# Board-Back.net
KiCad netlist of a schematic drawn in EAGLE
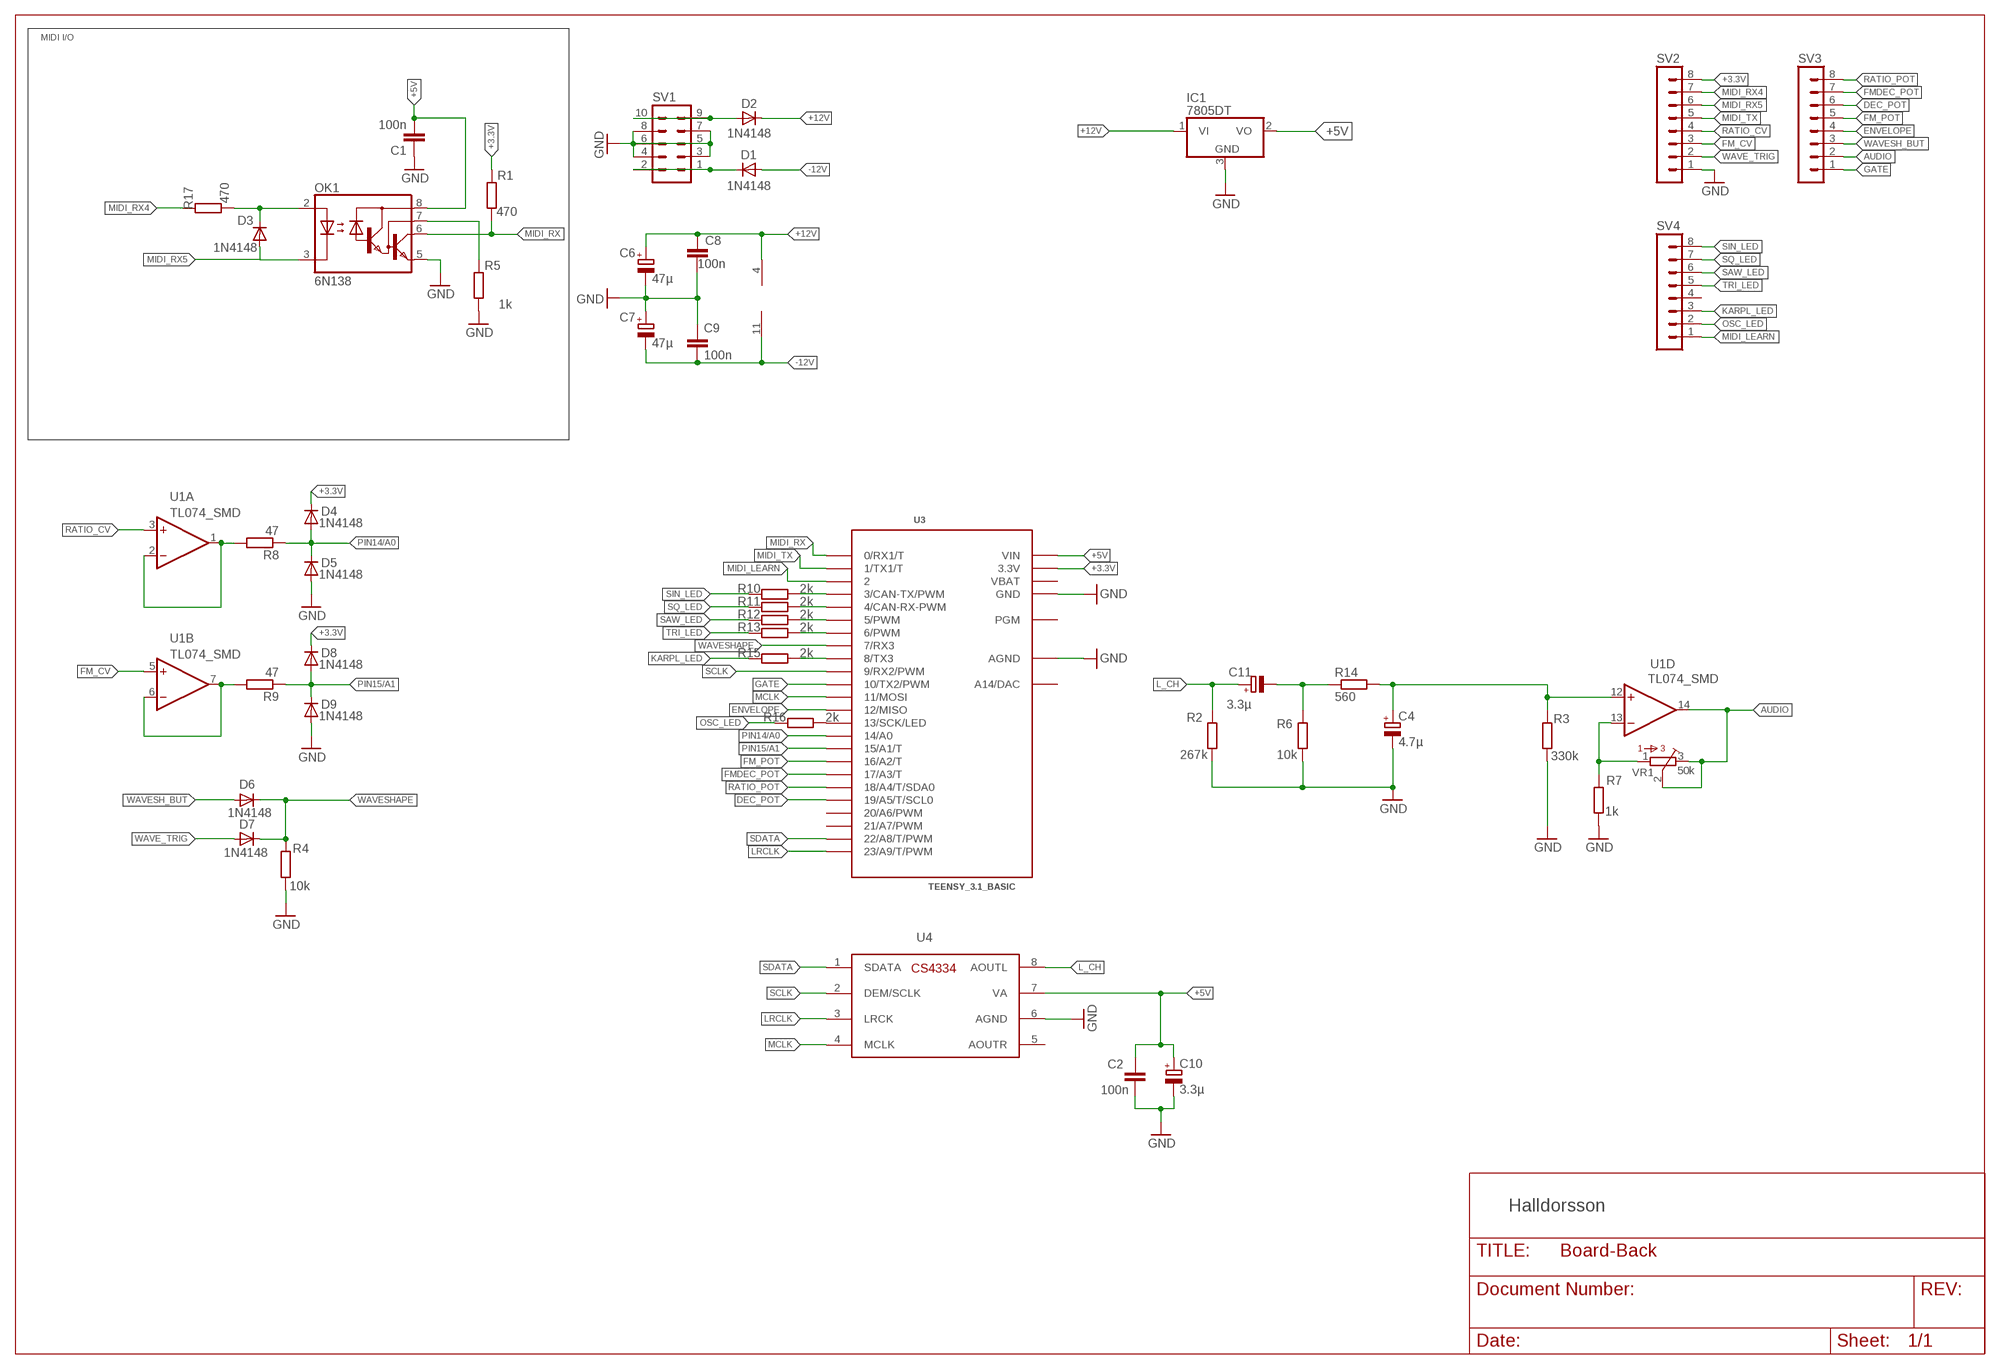
[diagram p0: schematic, sheet 1]

(export (version "E")
  (design (tool "Eeschema 10.0.6"))
  (components
    (comp (ref "C1")
      (value "100n")
      (footprint "eagle-import:C1206")
      (libsource (lib "eagle-import") (part "C-EUC1206"))
    )
    (comp (ref "C2")
      (value "100n")
      (footprint "eagle-import:C1206")
      (libsource (lib "eagle-import") (part "C-EUC1206"))
    )
    (comp (ref "C4")
      (value "4.7µ♦")
      (footprint "eagle-import:153CLV-0405")
      (libsource (lib "eagle-import") (part "CPOL-EU153CLV-0405"))
    )
    (comp (ref "C6")
      (value "47µ")
      (footprint "eagle-import:E5-6")
      (libsource (lib "eagle-import") (part "CPOL-EUE5-6"))
    )
    (comp (ref "C7")
      (value "47µ")
      (footprint "eagle-import:E5-6")
      (libsource (lib "eagle-import") (part "CPOL-EUE5-6"))
    )
    (comp (ref "C8")
      (value "100n")
      (footprint "eagle-import:C1206")
      (libsource (lib "eagle-import") (part "C-EUC1206"))
    )
    (comp (ref "C9")
      (value "100n")
      (footprint "eagle-import:C1206")
      (libsource (lib "eagle-import") (part "C-EUC1206"))
    )
    (comp (ref "C10")
      (value "3.3µ")
      (footprint "eagle-import:153CLV-0505")
      (libsource (lib "eagle-import") (part "CPOL-EU153CLV-0505"))
    )
    (comp (ref "C11")
      (value "3.3µ")
      (footprint "eagle-import:153CLV-0405")
      (libsource (lib "eagle-import") (part "CPOL-EU153CLV-0405"))
    )
    (comp (ref "D1")
      (value "1N4148")
      (footprint "eagle-import:DO35-7")
      (libsource (lib "eagle-import") (part "1N4148DO35-7"))
    )
    (comp (ref "D2")
      (value "1N4148")
      (footprint "eagle-import:DO35-7")
      (libsource (lib "eagle-import") (part "1N4148DO35-7"))
    )
    (comp (ref "D3")
      (value "1N4148")
      (footprint "eagle-import:DO35-7")
      (libsource (lib "eagle-import") (part "1N4148DO35-7"))
    )
    (comp (ref "D4")
      (value "1N4148")
      (footprint "eagle-import:DO35-7")
      (libsource (lib "eagle-import") (part "1N4148DO35-7"))
    )
    (comp (ref "D5")
      (value "1N4148")
      (footprint "eagle-import:DO35-7")
      (libsource (lib "eagle-import") (part "1N4148DO35-7"))
    )
    (comp (ref "D6")
      (value "1N4148")
      (footprint "eagle-import:DO35-7")
      (libsource (lib "eagle-import") (part "1N4148DO35-7"))
    )
    (comp (ref "D7")
      (value "1N4148")
      (footprint "eagle-import:DO35-7")
      (libsource (lib "eagle-import") (part "1N4148DO35-7"))
    )
    (comp (ref "D8")
      (value "1N4148")
      (footprint "eagle-import:DO35-7")
      (libsource (lib "eagle-import") (part "1N4148DO35-7"))
    )
    (comp (ref "D9")
      (value "1N4148")
      (footprint "eagle-import:DO35-7")
      (libsource (lib "eagle-import") (part "1N4148DO35-7"))
    )
    (comp (ref "IC1")
      (value "7805DT")
      (footprint "eagle-import:TO252")
      (libsource (lib "eagle-import") (part "78DT05"))
    )
    (comp (ref "OK1")
      (value "6N138")
      (footprint "eagle-import:DIL08")
      (fields (field (name "MF") "VISHAY/TELEFUNKEN"))
      (libsource (lib "eagle-import") (part "6N138"))
    )
    (comp (ref "R1")
      (value "470")
      (footprint "eagle-import:M1206")
      (libsource (lib "eagle-import") (part "R-EU_M1206"))
    )
    (comp (ref "R2")
      (value "267k")
      (footprint "eagle-import:M1206")
      (libsource (lib "eagle-import") (part "R-EU_M1206"))
    )
    (comp (ref "R3")
      (value "330k")
      (footprint "eagle-import:M1206")
      (libsource (lib "eagle-import") (part "R-EU_M1206"))
    )
    (comp (ref "R4")
      (value "10k")
      (footprint "eagle-import:M1206")
      (libsource (lib "eagle-import") (part "R-EU_M1206"))
    )
    (comp (ref "R5")
      (value "1k")
      (footprint "eagle-import:M1206")
      (libsource (lib "eagle-import") (part "R-EU_M1206"))
    )
    (comp (ref "R6")
      (value "10k")
      (footprint "eagle-import:M1206")
      (libsource (lib "eagle-import") (part "R-EU_M1206"))
    )
    (comp (ref "R7")
      (value "1k")
      (footprint "eagle-import:M1206")
      (libsource (lib "eagle-import") (part "R-EU_M1206"))
    )
    (comp (ref "R8")
      (value "47")
      (footprint "eagle-import:M1206")
      (libsource (lib "eagle-import") (part "R-EU_M1206"))
    )
    (comp (ref "R9")
      (value "47")
      (footprint "eagle-import:M1206")
      (libsource (lib "eagle-import") (part "R-EU_M1206"))
    )
    (comp (ref "R10")
      (value "2k")
      (footprint "eagle-import:M1206")
      (libsource (lib "eagle-import") (part "R-EU_M1206"))
    )
    (comp (ref "R11")
      (value "2k")
      (footprint "eagle-import:M1206")
      (libsource (lib "eagle-import") (part "R-EU_M1206"))
    )
    (comp (ref "R12")
      (value "2k")
      (footprint "eagle-import:M1206")
      (libsource (lib "eagle-import") (part "R-EU_M1206"))
    )
    (comp (ref "R13")
      (value "2k")
      (footprint "eagle-import:M1206")
      (libsource (lib "eagle-import") (part "R-EU_M1206"))
    )
    (comp (ref "R14")
      (value "560")
      (footprint "eagle-import:M1206")
      (libsource (lib "eagle-import") (part "R-EU_M1206"))
    )
    (comp (ref "R15")
      (value "2k")
      (footprint "eagle-import:M1206")
      (libsource (lib "eagle-import") (part "R-EU_M1206"))
    )
    (comp (ref "R16")
      (value "2k")
      (footprint "eagle-import:M1206")
      (libsource (lib "eagle-import") (part "R-EU_M1206"))
    )
    (comp (ref "R17")
      (value "470")
      (footprint "eagle-import:M1206")
      (libsource (lib "eagle-import") (part "R-EU_M1206"))
    )
    (comp (ref "SV1")
      (value "10PIN_BACKSIDE")
      (footprint "eagle-import:10PIN_BACKSIDE")
      (libsource (lib "eagle-import") (part "10PIN_BACKSIDE"))
    )
    (comp (ref "SV2")
      (value "MA08-1")
      (footprint "eagle-import:MA08-1")
      (libsource (lib "eagle-import") (part "MA08-1"))
    )
    (comp (ref "SV3")
      (value "MA08-1")
      (footprint "eagle-import:MA08-1")
      (libsource (lib "eagle-import") (part "MA08-1"))
    )
    (comp (ref "SV4")
      (value "MA08-1")
      (footprint "eagle-import:MA08-1")
      (libsource (lib "eagle-import") (part "MA08-1"))
    )
    (comp (ref "U1")
      (value "TL074_SMD")
      (footprint "eagle-import:SO14")
      (libsource (lib "eagle-import") (part "TL074_SMD"))
    )
    (comp (ref "U3")
      (value "TEENSY_3.1_BASIC")
      (footprint "eagle-import:TEENSY_3.1_BASIC")
      (libsource (lib "eagle-import") (part "TEENSY_3.1_BASIC"))
    )
    (comp (ref "U4")
      (value "CS4334")
      (footprint "eagle-import:SOIC127P600X175-8N")
      (libsource (lib "eagle-import") (part "CS4334"))
    )
    (comp (ref "VR1")
      (value "50k")
      (footprint "eagle-import:BOURNS_3362P_TRIMMER")
      (libsource (lib "eagle-import") (part "BOURNS_3362P_TRIMMERP"))
    )
  )
  (nets
    (net (code "1") (name "+3.3V") (class "Default")
      (node (ref "D4") (pin "C") (pinfunction "C_C") (pintype "passive"))
      (node (ref "D8") (pin "C") (pinfunction "C_C") (pintype "passive"))
      (node (ref "R1") (pin "2") (pinfunction "2_2") (pintype "passive"))
      (node (ref "SV2") (pin "8") (pinfunction "8_8") (pintype "passive"))
      (node (ref "U3") (pin "3.3V") (pinfunction "3.3V_3.3V") (pintype "power_in"))
      (node (ref "U3") (pin "3.3V1") (pinfunction "3.3V_3.3V1") (pintype "power_in"))
    )
    (net (code "2") (name "+5V") (class "Default")
      (node (ref "C1") (pin "2") (pinfunction "2_2") (pintype "passive"))
      (node (ref "C10") (pin "+") (pinfunction "+_+") (pintype "passive"))
      (node (ref "C2") (pin "1") (pinfunction "1_1") (pintype "passive"))
      (node (ref "IC1") (pin "2") (pinfunction "VO_2") (pintype "passive"))
      (node (ref "OK1") (pin "8") (pinfunction "VCC_8") (pintype "passive"))
      (node (ref "U3") (pin "VIN") (pinfunction "VIN_VIN") (pintype "power_in"))
      (node (ref "U4") (pin "7") (pinfunction "VA_7") (pintype "bidirectional"))
    )
    (net (code "3") (name "+12V") (class "Default")
      (node (ref "C6") (pin "+") (pinfunction "+_+") (pintype "passive"))
      (node (ref "C8") (pin "1") (pinfunction "1_1") (pintype "passive"))
      (node (ref "D2") (pin "C") (pinfunction "C_C") (pintype "passive"))
      (node (ref "IC1") (pin "1") (pinfunction "VI_1") (pintype "input"))
      (node (ref "U1") (pin "4") (pinfunction "V+_4") (pintype "power_in"))
    )
    (net (code "4") (name "-12V") (class "Default")
      (node (ref "C7") (pin "-") (pinfunction "-_-") (pintype "passive"))
      (node (ref "C9") (pin "2") (pinfunction "2_2") (pintype "passive"))
      (node (ref "D1") (pin "A") (pinfunction "A_A") (pintype "passive"))
      (node (ref "U1") (pin "11") (pinfunction "V-_11") (pintype "power_in"))
    )
    (net (code "5") (name "/VBAT") (class "Default")
      (node (ref "U3") (pin "VBAT") (pinfunction "VBAT_VBAT") (pintype "power_in"))
    )
    (net (code "6") (name "AUDIO") (class "Default")
      (node (ref "SV3") (pin "2") (pinfunction "2_2") (pintype "passive"))
      (node (ref "U1") (pin "14") (pinfunction "OUT_14") (pintype "output"))
      (node (ref "VR1") (pin "2") (pinfunction "2_2") (pintype "passive"))
      (node (ref "VR1") (pin "3") (pinfunction "3_3") (pintype "passive"))
    )
    (net (code "7") (name "DEC_POT") (class "Default")
      (node (ref "SV3") (pin "6") (pinfunction "6_6") (pintype "passive"))
      (node (ref "U3") (pin "19/A5") (pinfunction "19/A5/T/SCL0_19/A5") (pintype "bidirectional"))
    )
    (net (code "8") (name "ENVELOPE") (class "Default")
      (node (ref "SV3") (pin "4") (pinfunction "4_4") (pintype "passive"))
      (node (ref "U3") (pin "12") (pinfunction "12/MISO_12") (pintype "bidirectional"))
    )
    (net (code "9") (name "FMDEC_POT") (class "Default")
      (node (ref "SV3") (pin "7") (pinfunction "7_7") (pintype "passive"))
      (node (ref "U3") (pin "17/A3") (pinfunction "17/A3/T_17/A3") (pintype "bidirectional"))
    )
    (net (code "10") (name "FM_CV") (class "Default")
      (node (ref "SV2") (pin "3") (pinfunction "3_3") (pintype "passive"))
      (node (ref "U1") (pin "5") (pinfunction "+IN_5") (pintype "input"))
    )
    (net (code "11") (name "FM_POT") (class "Default")
      (node (ref "SV3") (pin "5") (pinfunction "5_5") (pintype "passive"))
      (node (ref "U3") (pin "16/A2") (pinfunction "16/A2/T_16/A2") (pintype "bidirectional"))
    )
    (net (code "12") (name "GATE") (class "Default")
      (node (ref "SV3") (pin "1") (pinfunction "1_1") (pintype "passive"))
      (node (ref "U3") (pin "10") (pinfunction "10/TX2/PWM_10") (pintype "bidirectional"))
    )
    (net (code "13") (name "GND") (class "Default")
      (node (ref "C1") (pin "1") (pinfunction "1_1") (pintype "passive"))
      (node (ref "C10") (pin "-") (pinfunction "-_-") (pintype "passive"))
      (node (ref "C2") (pin "2") (pinfunction "2_2") (pintype "passive"))
      (node (ref "C4") (pin "-") (pinfunction "-_-") (pintype "passive"))
      (node (ref "C6") (pin "-") (pinfunction "-_-") (pintype "passive"))
      (node (ref "C7") (pin "+") (pinfunction "+_+") (pintype "passive"))
      (node (ref "C8") (pin "2") (pinfunction "2_2") (pintype "passive"))
      (node (ref "C9") (pin "1") (pinfunction "1_1") (pintype "passive"))
      (node (ref "D5") (pin "A") (pinfunction "A_A") (pintype "passive"))
      (node (ref "D9") (pin "A") (pinfunction "A_A") (pintype "passive"))
      (node (ref "IC1") (pin "3") (pinfunction "GND_3") (pintype "passive"))
      (node (ref "OK1") (pin "5") (pinfunction "GND_5") (pintype "passive"))
      (node (ref "R2") (pin "2") (pinfunction "2_2") (pintype "passive"))
      (node (ref "R3") (pin "2") (pinfunction "2_2") (pintype "passive"))
      (node (ref "R4") (pin "1") (pinfunction "1_1") (pintype "passive"))
      (node (ref "R5") (pin "1") (pinfunction "1_1") (pintype "passive"))
      (node (ref "R6") (pin "2") (pinfunction "2_2") (pintype "passive"))
      (node (ref "R7") (pin "2") (pinfunction "2_2") (pintype "passive"))
      (node (ref "SV1") (pin "3") (pinfunction "3_3") (pintype "passive"))
      (node (ref "SV1") (pin "4") (pinfunction "4_4") (pintype "passive"))
      (node (ref "SV1") (pin "5") (pinfunction "5_5") (pintype "passive"))
      (node (ref "SV1") (pin "6") (pinfunction "6_6") (pintype "passive"))
      (node (ref "SV1") (pin "7") (pinfunction "7_7") (pintype "passive"))
      (node (ref "SV1") (pin "8") (pinfunction "8_8") (pintype "passive"))
      (node (ref "SV2") (pin "1") (pinfunction "1_1") (pintype "passive"))
      (node (ref "U3") (pin "AGND") (pinfunction "AGND_AGND") (pintype "power_in"))
      (node (ref "U3") (pin "GND") (pinfunction "GND_GND") (pintype "power_in"))
      (node (ref "U3") (pin "GND1") (pinfunction "GND_GND1") (pintype "power_in"))
      (node (ref "U4") (pin "6") (pinfunction "AGND_6") (pintype "bidirectional"))
    )
    (net (code "14") (name "KARPL_LED") (class "Default")
      (node (ref "R15") (pin "2") (pinfunction "2_2") (pintype "passive"))
      (node (ref "SV4") (pin "3") (pinfunction "3_3") (pintype "passive"))
    )
    (net (code "15") (name "LRCLK") (class "Default")
      (node (ref "U3") (pin "23/A9") (pinfunction "23/A9/T/PWM_23/A9") (pintype "bidirectional"))
      (node (ref "U4") (pin "3") (pinfunction "LRCK_3") (pintype "bidirectional"))
    )
    (net (code "16") (name "L_CH") (class "Default")
      (node (ref "C11") (pin "+") (pinfunction "+_+") (pintype "passive"))
      (node (ref "R2") (pin "1") (pinfunction "1_1") (pintype "passive"))
      (node (ref "U4") (pin "8") (pinfunction "AOUTL_8") (pintype "bidirectional"))
    )
    (net (code "17") (name "MCLK") (class "Default")
      (node (ref "U3") (pin "11") (pinfunction "11/MOSI_11") (pintype "bidirectional"))
      (node (ref "U4") (pin "4") (pinfunction "MCLK_4") (pintype "bidirectional"))
    )
    (net (code "18") (name "MIDI_LEARN") (class "Default")
      (node (ref "SV4") (pin "1") (pinfunction "1_1") (pintype "passive"))
      (node (ref "U3") (pin "2") (pinfunction "2_2") (pintype "bidirectional"))
    )
    (net (code "19") (name "MIDI_RX") (class "Default")
      (node (ref "OK1") (pin "6") (pinfunction "VO_6") (pintype "passive"))
      (node (ref "R1") (pin "1") (pinfunction "1_1") (pintype "passive"))
      (node (ref "U3") (pin "0") (pinfunction "0/RX1/T_0") (pintype "bidirectional"))
    )
    (net (code "20") (name "MIDI_RX4") (class "Default")
      (node (ref "R17") (pin "2") (pinfunction "2_2") (pintype "passive"))
      (node (ref "SV2") (pin "7") (pinfunction "7_7") (pintype "passive"))
    )
    (net (code "21") (name "MIDI_RX5") (class "Default")
      (node (ref "D3") (pin "A") (pinfunction "A_A") (pintype "passive"))
      (node (ref "OK1") (pin "3") (pinfunction "C_3") (pintype "passive"))
      (node (ref "SV2") (pin "6") (pinfunction "6_6") (pintype "passive"))
    )
    (net (code "22") (name "MIDI_TX") (class "Default")
      (node (ref "SV2") (pin "5") (pinfunction "5_5") (pintype "passive"))
      (node (ref "U3") (pin "1") (pinfunction "1/TX1/T_1") (pintype "bidirectional"))
    )
    (net (code "23") (name "Net-(C11-Pad-)") (class "Default")
      (node (ref "C11") (pin "-") (pinfunction "-_-") (pintype "passive"))
      (node (ref "R14") (pin "1") (pinfunction "1_1") (pintype "passive"))
      (node (ref "R6") (pin "1") (pinfunction "1_1") (pintype "passive"))
    )
    (net (code "24") (name "Net-(D1-PadC)") (class "Default")
      (node (ref "D1") (pin "C") (pinfunction "C_C") (pintype "passive"))
      (node (ref "SV1") (pin "1") (pinfunction "1_1") (pintype "passive"))
      (node (ref "SV1") (pin "2") (pinfunction "2_2") (pintype "passive"))
    )
    (net (code "25") (name "Net-(D2-PadA)") (class "Default")
      (node (ref "D2") (pin "A") (pinfunction "A_A") (pintype "passive"))
      (node (ref "SV1") (pin "10") (pinfunction "10_10") (pintype "passive"))
      (node (ref "SV1") (pin "9") (pinfunction "9_9") (pintype "passive"))
    )
    (net (code "26") (name "Net-(OK1-A)") (class "Default")
      (node (ref "D3") (pin "C") (pinfunction "C_C") (pintype "passive"))
      (node (ref "OK1") (pin "2") (pinfunction "A_2") (pintype "passive"))
      (node (ref "R17") (pin "1") (pinfunction "1_1") (pintype "passive"))
    )
    (net (code "27") (name "Net-(OK1-VB)") (class "Default")
      (node (ref "OK1") (pin "7") (pinfunction "VB_7") (pintype "passive"))
      (node (ref "R5") (pin "2") (pinfunction "2_2") (pintype "passive"))
    )
    (net (code "28") (name "Net-(U1A--IN)") (class "Default")
      (node (ref "R8") (pin "2") (pinfunction "2_2") (pintype "passive"))
      (node (ref "U1") (pin "1") (pinfunction "OUT_1") (pintype "output"))
      (node (ref "U1") (pin "2") (pinfunction "-IN_2") (pintype "input"))
    )
    (net (code "29") (name "Net-(U1B--IN)") (class "Default")
      (node (ref "R9") (pin "2") (pinfunction "2_2") (pintype "passive"))
      (node (ref "U1") (pin "6") (pinfunction "-IN_6") (pintype "input"))
      (node (ref "U1") (pin "7") (pinfunction "OUT_7") (pintype "output"))
    )
    (net (code "30") (name "Net-(U1D-+IN)") (class "Default")
      (node (ref "C4") (pin "+") (pinfunction "+_+") (pintype "passive"))
      (node (ref "R14") (pin "2") (pinfunction "2_2") (pintype "passive"))
      (node (ref "R3") (pin "1") (pinfunction "1_1") (pintype "passive"))
      (node (ref "U1") (pin "12") (pinfunction "+IN_12") (pintype "input"))
    )
    (net (code "31") (name "Net-(U1D--IN)") (class "Default")
      (node (ref "R7") (pin "1") (pinfunction "1_1") (pintype "passive"))
      (node (ref "U1") (pin "13") (pinfunction "-IN_13") (pintype "input"))
      (node (ref "VR1") (pin "1") (pinfunction "1_1") (pintype "passive"))
    )
    (net (code "32") (name "Net-(U3-3{slash}CAN-TX{slash}PWM)") (class "Default")
      (node (ref "R10") (pin "1") (pinfunction "1_1") (pintype "passive"))
      (node (ref "U3") (pin "3") (pinfunction "3/CAN-TX/PWM_3") (pintype "bidirectional"))
    )
    (net (code "33") (name "Net-(U3-4{slash}CAN-RX-PWM)") (class "Default")
      (node (ref "R11") (pin "1") (pinfunction "1_1") (pintype "passive"))
      (node (ref "U3") (pin "4") (pinfunction "4/CAN-RX-PWM_4") (pintype "bidirectional"))
    )
    (net (code "34") (name "Net-(U3-5{slash}PWM)") (class "Default")
      (node (ref "R12") (pin "1") (pinfunction "1_1") (pintype "passive"))
      (node (ref "U3") (pin "5") (pinfunction "5/PWM_5") (pintype "bidirectional"))
    )
    (net (code "35") (name "Net-(U3-6{slash}PWM)") (class "Default")
      (node (ref "R13") (pin "1") (pinfunction "1_1") (pintype "passive"))
      (node (ref "U3") (pin "6") (pinfunction "6/PWM_6") (pintype "bidirectional"))
    )
    (net (code "36") (name "Net-(U3-8{slash}TX3)") (class "Default")
      (node (ref "R15") (pin "1") (pinfunction "1_1") (pintype "passive"))
      (node (ref "U3") (pin "8") (pinfunction "8/TX3_8") (pintype "bidirectional"))
    )
    (net (code "37") (name "Net-(U3-13{slash}SCK{slash}LED)") (class "Default")
      (node (ref "R16") (pin "1") (pinfunction "1_1") (pintype "passive"))
      (node (ref "U3") (pin "13") (pinfunction "13/SCK/LED_13") (pintype "bidirectional"))
    )
    (net (code "38") (name "OSC_LED") (class "Default")
      (node (ref "R16") (pin "2") (pinfunction "2_2") (pintype "passive"))
      (node (ref "SV4") (pin "2") (pinfunction "2_2") (pintype "passive"))
    )
    (net (code "39") (name "PIN14{slash}A0") (class "Default")
      (node (ref "D4") (pin "A") (pinfunction "A_A") (pintype "passive"))
      (node (ref "D5") (pin "C") (pinfunction "C_C") (pintype "passive"))
      (node (ref "R8") (pin "1") (pinfunction "1_1") (pintype "passive"))
      (node (ref "U3") (pin "14/A0") (pinfunction "14/A0_14/A0") (pintype "bidirectional"))
    )
    (net (code "40") (name "PIN15{slash}A1") (class "Default")
      (node (ref "D8") (pin "A") (pinfunction "A_A") (pintype "passive"))
      (node (ref "D9") (pin "C") (pinfunction "C_C") (pintype "passive"))
      (node (ref "R9") (pin "1") (pinfunction "1_1") (pintype "passive"))
      (node (ref "U3") (pin "15/A1") (pinfunction "15/A1/T_15/A1") (pintype "bidirectional"))
    )
    (net (code "41") (name "RATIO_CV") (class "Default")
      (node (ref "SV2") (pin "4") (pinfunction "4_4") (pintype "passive"))
      (node (ref "U1") (pin "3") (pinfunction "+IN_3") (pintype "input"))
    )
    (net (code "42") (name "RATIO_POT") (class "Default")
      (node (ref "SV3") (pin "8") (pinfunction "8_8") (pintype "passive"))
      (node (ref "U3") (pin "18/A4") (pinfunction "18/A4/T/SDA0_18/A4") (pintype "bidirectional"))
    )
    (net (code "43") (name "SAW_LED") (class "Default")
      (node (ref "R12") (pin "2") (pinfunction "2_2") (pintype "passive"))
      (node (ref "SV4") (pin "6") (pinfunction "6_6") (pintype "passive"))
    )
    (net (code "44") (name "SCLK") (class "Default")
      (node (ref "U3") (pin "9") (pinfunction "9/RX2/PWM_9") (pintype "bidirectional"))
      (node (ref "U4") (pin "2") (pinfunction "DEM/SCLK_2") (pintype "bidirectional"))
    )
    (net (code "45") (name "SDATA") (class "Default")
      (node (ref "U3") (pin "22/A8") (pinfunction "22/A8/T/PWM_22/A8") (pintype "bidirectional"))
      (node (ref "U4") (pin "1") (pinfunction "SDATA_1") (pintype "bidirectional"))
    )
    (net (code "46") (name "SIN_LED") (class "Default")
      (node (ref "R10") (pin "2") (pinfunction "2_2") (pintype "passive"))
      (node (ref "SV4") (pin "8") (pinfunction "8_8") (pintype "passive"))
    )
    (net (code "47") (name "SQ_LED") (class "Default")
      (node (ref "R11") (pin "2") (pinfunction "2_2") (pintype "passive"))
      (node (ref "SV4") (pin "7") (pinfunction "7_7") (pintype "passive"))
    )
    (net (code "48") (name "TRI_LED") (class "Default")
      (node (ref "R13") (pin "2") (pinfunction "2_2") (pintype "passive"))
      (node (ref "SV4") (pin "5") (pinfunction "5_5") (pintype "passive"))
    )
    (net (code "49") (name "WAVESHAPE") (class "Default")
      (node (ref "D6") (pin "C") (pinfunction "C_C") (pintype "passive"))
      (node (ref "D7") (pin "C") (pinfunction "C_C") (pintype "passive"))
      (node (ref "R4") (pin "2") (pinfunction "2_2") (pintype "passive"))
      (node (ref "U3") (pin "7") (pinfunction "7/RX3_7") (pintype "bidirectional"))
    )
    (net (code "50") (name "WAVESH_BUT") (class "Default")
      (node (ref "D6") (pin "A") (pinfunction "A_A") (pintype "passive"))
      (node (ref "SV3") (pin "3") (pinfunction "3_3") (pintype "passive"))
    )
    (net (code "51") (name "WAVE_TRIG") (class "Default")
      (node (ref "D7") (pin "A") (pinfunction "A_A") (pintype "passive"))
      (node (ref "SV2") (pin "2") (pinfunction "2_2") (pintype "passive"))
    )
    (net (code "52") (name "unconnected-(SV4-Pad4)") (class "Default")
      (node (ref "SV4") (pin "4") (pinfunction "4_4") (pintype "passive"))
    )
    (net (code "53") (name "unconnected-(U3-20{slash}A6{slash}PWM-Pad20{slash}A6)") (class "Default")
      (node (ref "U3") (pin "20/A6") (pinfunction "20/A6/PWM_20/A6") (pintype "bidirectional"))
    )
    (net (code "54") (name "unconnected-(U3-21{slash}A7{slash}PWM-Pad21{slash}A7)") (class "Default")
      (node (ref "U3") (pin "21/A7") (pinfunction "21/A7/PWM_21/A7") (pintype "bidirectional"))
    )
    (net (code "55") (name "unconnected-(U3-A14{slash}DAC-PadA14)") (class "Default")
      (node (ref "U3") (pin "A14") (pinfunction "A14/DAC_A14") (pintype "bidirectional"))
    )
    (net (code "56") (name "unconnected-(U3-PadPGM)") (class "Default")
      (node (ref "U3") (pin "PGM") (pinfunction "PGM_PGM") (pintype "bidirectional"))
    )
    (net (code "57") (name "unconnected-(U4-AOUTR-Pad5)") (class "Default")
      (node (ref "U4") (pin "5") (pinfunction "AOUTR_5") (pintype "bidirectional"))
    )
  )
)
